# pca10031_misc.net
KiCad netlist of a schematic drawn in Altium Designer
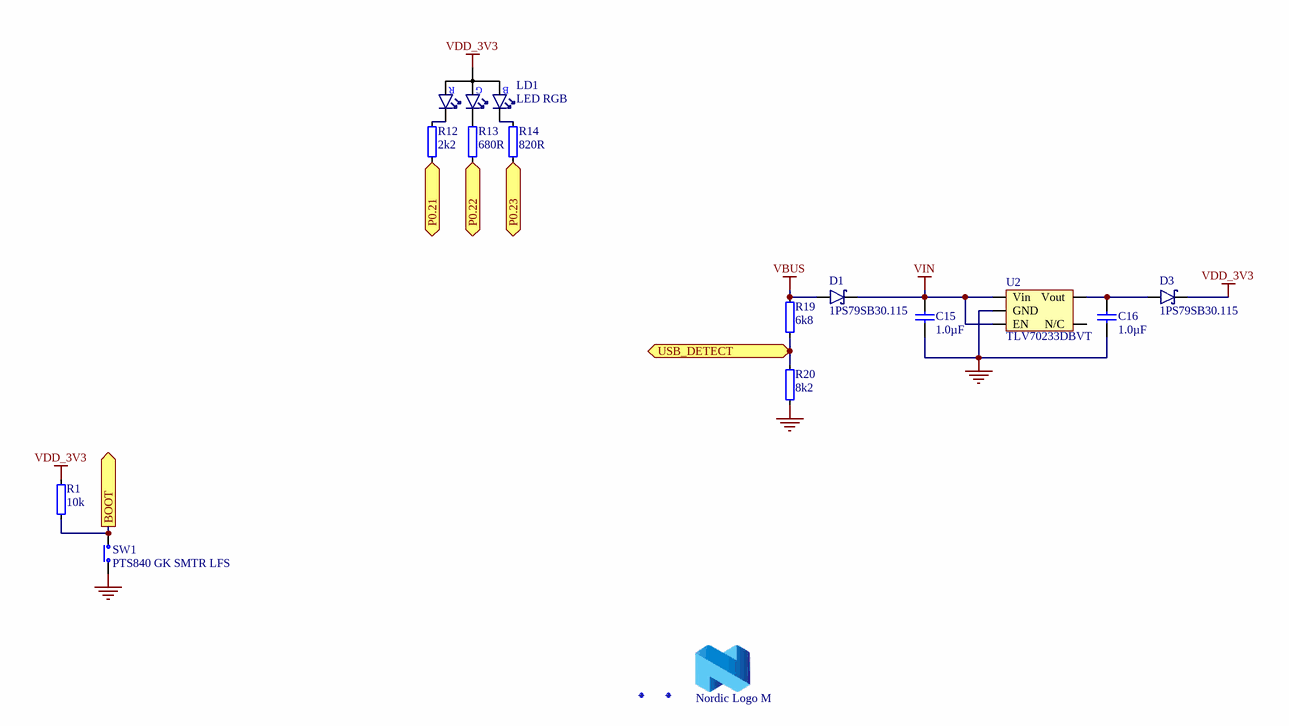
[diagram p0: pca10031_misc.SchDoc]

(export (version "E")
  (design (tool "Eeschema 10.0.6"))
  (components
    (comp (ref "C15")
      (value "1.0µF")
      (footprint "CAPC1608X06L")
      (description "Capacitor, X7R, ±10%")
      (fields (field (name "PART NUMBER") "C0603-1µ0") (field (name "PUBLISHER") "Nordic Semiconductor"))
      (libsource (lib "Nordic Passive DB") (part "CAP"))
    )
    (comp (ref "C16")
      (value "1.0µF")
      (footprint "CAPC1608X06L")
      (description "Capacitor, X7R, ±10%")
      (fields (field (name "PART NUMBER") "C0603-1µ0") (field (name "PUBLISHER") "Nordic Semiconductor"))
      (libsource (lib "Nordic Passive DB") (part "CAP"))
    )
    (comp (ref "D1")
      (value "1PS79SB30.115")
      (footprint "SOD-523")
      (description "Diode Schottky Vf=0.38, Vr=40V, If=200mA, Ir=500nA")
      (fields (field (name "MANUFACTURER") "NXP") (field (name "PUBLISHER") "Nordic Semiconductor"))
      (libsource (lib "Nordic Discrete DB") (part "D{colon}SCHOTTKY"))
    )
    (comp (ref "D3")
      (value "1PS79SB30.115")
      (footprint "SOD-523")
      (description "Diode Schottky Vf=0.38, Vr=40V, If=200mA, Ir=500nA")
      (fields (field (name "MANUFACTURER") "NXP") (field (name "PUBLISHER") "Nordic Semiconductor"))
      (libsource (lib "Nordic Discrete DB") (part "D{colon}SCHOTTKY"))
    )
    (comp (ref "Fid1")
      (value "Fiducial mark")
      (footprint "Fiducial")
      (description "Fiducial Mark")
      (fields (field (name "PART NUMBER") "Fid-Mark") (field (name "PUBLISHER") "Nordic Semiconductor"))
      (libsource (lib "Nordic Passive DB") (part "Fiducial"))
    )
    (comp (ref "Fid2")
      (value "Fiducial mark")
      (footprint "Fiducial")
      (description "Fiducial Mark")
      (fields (field (name "PART NUMBER") "Fid-Mark") (field (name "PUBLISHER") "Nordic Semiconductor"))
      (libsource (lib "Nordic Passive DB") (part "Fiducial"))
    )
    (comp (ref "LD1")
      (value "LED RGB")
      (footprint "SML-LX0404SIUPGUSB")
      (description "RGB LED 1.00 mm x 1.00 mm SMD")
      (fields
        (field (name "PART NUMBER") "SML-LX0404SIUPGUSB")
        (field (name "MANUFACTURER") "Lumex")
        (field (name "PUBLISHER") "Nordic Semiconductor")
      )
      (libsource (lib "Nordic Discrete DB") (part "D{colon}LED_RGB"))
    )
    (comp (ref "LOGO1")
      (value "Nordic Logo M")
      (footprint "NORDIC_LOGO_M")
      (description "Nordic Logo, medium size")
      (fields (field (name "PUBLISHER") "Nordic Semiconductor"))
      (libsource (lib "Nordic Passive DB") (part "Nordic Logo"))
    )
    (comp (ref "R1")
      (value "10k")
      (footprint "RESC1005X04L")
      (description "Resistor, ±1%, 0.063W")
      (fields (field (name "PART NUMBER") "R0402-10k") (field (name "PUBLISHER") "Nordic Semiconductor"))
      (libsource (lib "Nordic Passive DB") (part "RES_1"))
    )
    (comp (ref "R12")
      (value "2k2")
      (footprint "RESC1005X04L")
      (description "Resistor, ±1%, 0.063W")
      (fields (field (name "PART NUMBER") "R0402-2k2") (field (name "PUBLISHER") "Nordic Semiconductor"))
      (libsource (lib "Nordic Passive DB") (part "RES_1"))
    )
    (comp (ref "R13")
      (value "680R")
      (footprint "RESC1005X04L")
      (description "Resistor, ±1%, 0.063W")
      (fields (field (name "PART NUMBER") "R0402-680") (field (name "PUBLISHER") "Nordic Semiconductor"))
      (libsource (lib "Nordic Passive DB") (part "RES_1"))
    )
    (comp (ref "R14")
      (value "820R")
      (footprint "RESC1005X04L")
      (description "Resistor, ±1%, 0.063W")
      (fields (field (name "PART NUMBER") "R0402-820") (field (name "PUBLISHER") "Nordic Semiconductor"))
      (libsource (lib "Nordic Passive DB") (part "RES_1"))
    )
    (comp (ref "R19")
      (value "6k8")
      (footprint "RESC1005X04L")
      (description "Resistor, ±1%, 0.063W")
      (fields (field (name "PART NUMBER") "R0402-6k8") (field (name "PUBLISHER") "Nordic Semiconductor"))
      (libsource (lib "Nordic Passive DB") (part "RES_1"))
    )
    (comp (ref "R20")
      (value "8k2")
      (footprint "RESC1005X04L")
      (description "Resistor, ±1%, 0.063W")
      (fields (field (name "PART NUMBER") "R0402-8k2") (field (name "PUBLISHER") "Nordic Semiconductor"))
      (libsource (lib "Nordic Passive DB") (part "RES_1"))
    )
    (comp (ref "SW1")
      (value "PTS840 GK SMTR LFS")
      (footprint "EVQP7A/J/B/K")
      (description "Microminiature SMT Switch, Side Actuated")
      (fields
        (field (name "MANUFACTURER") "C & K")
        (field (name "2ND SOURCE PART NUMBER") "611-PTS840GKSMTR")
        (field (name "PUBLISHER") "Nordic Semiconductor")
      )
      (libsource (lib "Nordic Discrete DB") (part "SW-PB"))
    )
    (comp (ref "U2")
      (value "TLV70233DBVT")
      (footprint "SOT-23-5")
      (description "IC REG LDO 3.3V 300MA SOT23-5")
      (fields
        (field (name "MANUFACTURER") "Texas Instruments")
        (field (name "PUBLISHER") "Nordic Semiconductor")
      )
      (libsource (lib "Nordic Active DB") (part "TLV702xxDBV"))
    )
  )
  (nets
    (net (code "1") (name "/BOOT") (class "Default")
      (node (ref "R1") (pin "1") (pinfunction "1_1") (pintype "passive"))
      (node (ref "SW1") (pin "1") (pinfunction "N.O_1") (pintype "passive"))
    )
    (net (code "2") (name "/P0.21") (class "Default")
      (node (ref "R12") (pin "1") (pinfunction "1_1") (pintype "passive"))
    )
    (net (code "3") (name "/P0.22") (class "Default")
      (node (ref "R13") (pin "1") (pinfunction "1_1") (pintype "passive"))
    )
    (net (code "4") (name "/P0.23") (class "Default")
      (node (ref "R14") (pin "1") (pinfunction "1_1") (pintype "passive"))
    )
    (net (code "5") (name "/USB_DETECT") (class "Default")
      (node (ref "R19") (pin "2") (pinfunction "2_2") (pintype "passive"))
      (node (ref "R20") (pin "1") (pinfunction "1_1") (pintype "passive"))
    )
    (net (code "6") (name "GND") (class "Default")
      (node (ref "C15") (pin "1") (pinfunction "1_1") (pintype "passive"))
      (node (ref "C16") (pin "1") (pinfunction "1_1") (pintype "passive"))
      (node (ref "R20") (pin "2") (pinfunction "2_2") (pintype "passive"))
      (node (ref "SW1") (pin "2") (pinfunction "COM_2") (pintype "passive"))
      (node (ref "U2") (pin "2") (pinfunction "GND_2") (pintype "passive"))
    )
    (net (code "7") (name "Net-(D3-A)") (class "Default")
      (node (ref "C16") (pin "2") (pinfunction "2_2") (pintype "passive"))
      (node (ref "D3") (pin "1") (pinfunction "A_1") (pintype "passive"))
      (node (ref "U2") (pin "5") (pinfunction "Vout_5") (pintype "passive"))
    )
    (net (code "8") (name "Net-(LD1-C_BLUE)") (class "Default")
      (node (ref "LD1") (pin "3") (pinfunction "C_BLUE_3") (pintype "passive"))
      (node (ref "R14") (pin "2") (pinfunction "2_2") (pintype "passive"))
    )
    (net (code "9") (name "Net-(LD1-C_GREEN)") (class "Default")
      (node (ref "LD1") (pin "2") (pinfunction "C_GREEN_2") (pintype "passive"))
      (node (ref "R13") (pin "2") (pinfunction "2_2") (pintype "passive"))
    )
    (net (code "10") (name "Net-(LD1-C_RED)") (class "Default")
      (node (ref "LD1") (pin "1") (pinfunction "C_RED_1") (pintype "passive"))
      (node (ref "R12") (pin "2") (pinfunction "2_2") (pintype "passive"))
    )
    (net (code "11") (name "VBUS") (class "Default")
      (node (ref "D1") (pin "1") (pinfunction "A_1") (pintype "passive"))
      (node (ref "R19") (pin "1") (pinfunction "1_1") (pintype "passive"))
    )
    (net (code "12") (name "VDD_3V3") (class "Default")
      (node (ref "D3") (pin "3") (pinfunction "C_3") (pintype "passive"))
      (node (ref "LD1") (pin "4") (pinfunction "A_4") (pintype "passive"))
      (node (ref "R1") (pin "2") (pinfunction "2_2") (pintype "passive"))
    )
    (net (code "13") (name "VIN") (class "Default")
      (node (ref "C15") (pin "2") (pinfunction "2_2") (pintype "passive"))
      (node (ref "D1") (pin "3") (pinfunction "C_3") (pintype "passive"))
      (node (ref "U2") (pin "1") (pinfunction "Vin_1") (pintype "passive"))
      (node (ref "U2") (pin "3") (pinfunction "EN_3") (pintype "passive"))
    )
    (net (code "14") (name "unconnected-(U2-N{slash}C-Pad4)") (class "Default")
      (node (ref "U2") (pin "4") (pinfunction "N/C_4") (pintype "passive"))
    )
  )
)
